# abr.net
KiCad netlist of a schematic drawn in EAGLE
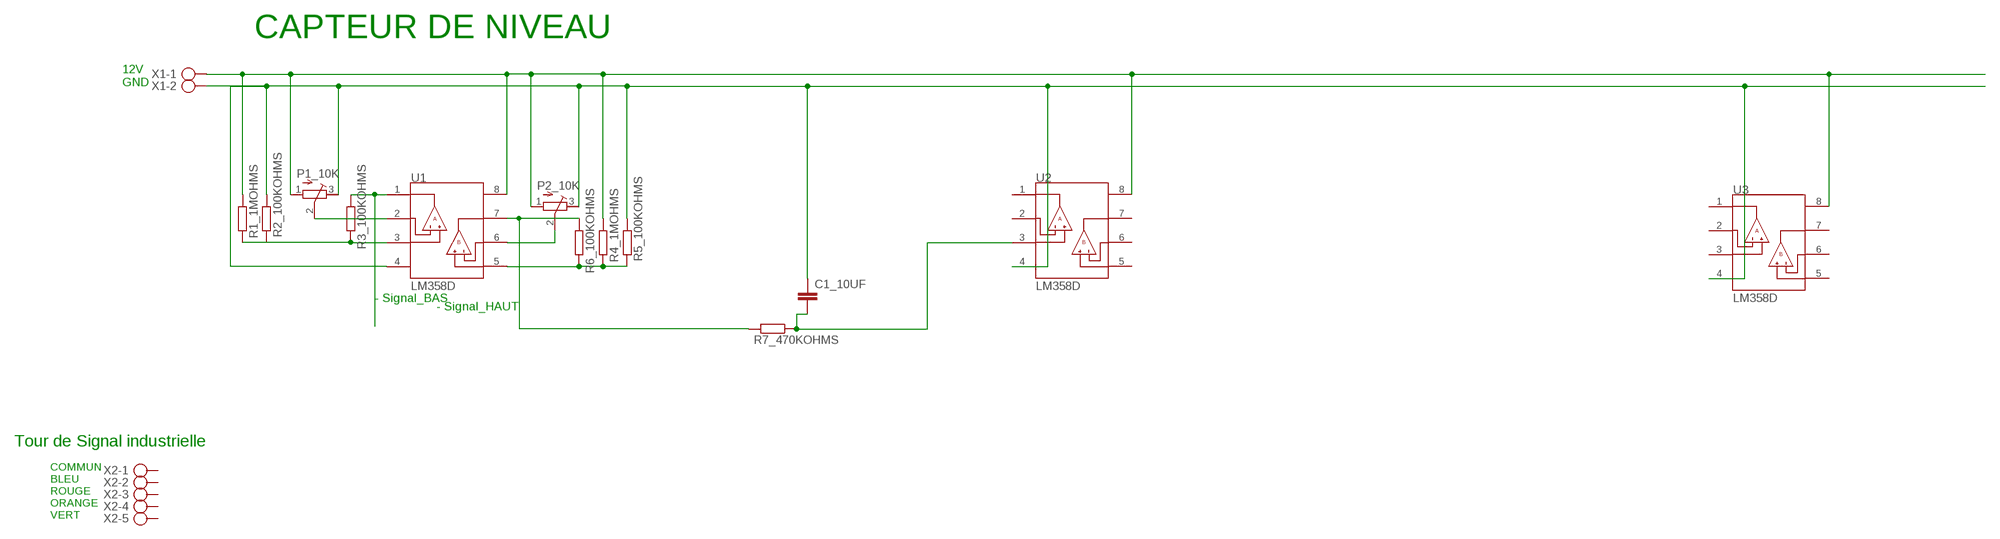
[diagram p0: schematic, sheet 1]

(export (version "E")
  (design (tool "Eeschema 10.0.6"))
  (components
    (comp (ref "C1_10UF")
      (value "C-EU025-025X050")
      (footprint "eagle-import:C025-025X050")
      (libsource (lib "eagle-import") (part "C-EU025-025X050"))
    )
    (comp (ref "P1_10K")
      (value "R-TRIMM3339P")
      (footprint "eagle-import:RTRIM3339P")
      (libsource (lib "eagle-import") (part "R-TRIMM3339P"))
    )
    (comp (ref "P2_10K")
      (value "R-TRIMM3339P")
      (footprint "eagle-import:RTRIM3339P")
      (libsource (lib "eagle-import") (part "R-TRIMM3339P"))
    )
    (comp (ref "R1_1MOHMS")
      (value "R-EU_0207/10")
      (footprint "eagle-import:0207_10")
      (libsource (lib "eagle-import") (part "R-EU_0207/10"))
    )
    (comp (ref "R2_100KOHMS")
      (value "R-EU_0207/10")
      (footprint "eagle-import:0207_10")
      (libsource (lib "eagle-import") (part "R-EU_0207/10"))
    )
    (comp (ref "R3_100KOHMS")
      (value "R-EU_0207/10")
      (footprint "eagle-import:0207_10")
      (libsource (lib "eagle-import") (part "R-EU_0207/10"))
    )
    (comp (ref "R4_1MOHMS")
      (value "R-EU_0207/10")
      (footprint "eagle-import:0207_10")
      (libsource (lib "eagle-import") (part "R-EU_0207/10"))
    )
    (comp (ref "R5_100KOHMS")
      (value "R-EU_0207/10")
      (footprint "eagle-import:0207_10")
      (libsource (lib "eagle-import") (part "R-EU_0207/10"))
    )
    (comp (ref "R6_100KOHMS")
      (value "R-EU_0207/10")
      (footprint "eagle-import:0207_10")
      (libsource (lib "eagle-import") (part "R-EU_0207/10"))
    )
    (comp (ref "R7_470KOHMS")
      (value "R-EU_0207/10")
      (footprint "eagle-import:0207_10")
      (libsource (lib "eagle-import") (part "R-EU_0207/10"))
    )
    (comp (ref "U1")
      (value "LM358D")
      (footprint "eagle-import:SOIC127P599X175-8N")
      (fields (field (name "MF") "STMicroelectronics"))
      (libsource (lib "eagle-import") (part "LM358D"))
    )
    (comp (ref "U2")
      (value "LM358D")
      (footprint "eagle-import:SOIC127P599X175-8N")
      (fields (field (name "MF") "STMicroelectronics"))
      (libsource (lib "eagle-import") (part "LM358D"))
    )
    (comp (ref "U3")
      (value "LM358D")
      (footprint "eagle-import:SOIC127P599X175-8N")
      (fields (field (name "MF") "STMicroelectronics"))
      (libsource (lib "eagle-import") (part "LM358D"))
    )
    (comp (ref "X1")
      (value "AK300/2")
      (footprint "eagle-import:AK300_2")
      (libsource (lib "eagle-import") (part "AK300/2"))
    )
    (comp (ref "X2")
      (value "AK300/5")
      (footprint "eagle-import:AK300_5")
      (libsource (lib "eagle-import") (part "AK300/5"))
    )
  )
  (nets
    (net (code "1") (name "Net-(P1_10K-A)") (class "Default")
      (node (ref "P1_10K") (pin "1") (pinfunction "A_1") (pintype "passive"))
      (node (ref "P2_10K") (pin "1") (pinfunction "A_1") (pintype "passive"))
      (node (ref "R1_1MOHMS") (pin "1") (pinfunction "1_1") (pintype "passive"))
      (node (ref "R4_1MOHMS") (pin "1") (pinfunction "1_1") (pintype "passive"))
      (node (ref "U1") (pin "8") (pinfunction "V+_8") (pintype "power_in"))
      (node (ref "U2") (pin "8") (pinfunction "V+_8") (pintype "power_in"))
      (node (ref "U3") (pin "8") (pinfunction "V+_8") (pintype "power_in"))
      (node (ref "X1") (pin "1") (pinfunction "KL_1") (pintype "passive"))
    )
    (net (code "2") (name "Net-(P1_10K-E)") (class "Default")
      (node (ref "C1_10UF") (pin "1") (pinfunction "1_1") (pintype "passive"))
      (node (ref "P1_10K") (pin "3") (pinfunction "E_3") (pintype "passive"))
      (node (ref "P2_10K") (pin "3") (pinfunction "E_3") (pintype "passive"))
      (node (ref "R2_100KOHMS") (pin "1") (pinfunction "1_1") (pintype "passive"))
      (node (ref "R5_100KOHMS") (pin "1") (pinfunction "1_1") (pintype "passive"))
      (node (ref "U1") (pin "4") (pinfunction "V-_4") (pintype "power_in"))
      (node (ref "U2") (pin "4") (pinfunction "V-_4") (pintype "power_in"))
      (node (ref "U3") (pin "4") (pinfunction "V-_4") (pintype "power_in"))
      (node (ref "X1") (pin "2") (pinfunction "KL_2") (pintype "passive"))
    )
    (net (code "3") (name "Net-(P1_10K-S)") (class "Default")
      (node (ref "P1_10K") (pin "2") (pinfunction "S_2") (pintype "passive"))
      (node (ref "U1") (pin "2") (pinfunction "IN1-_2") (pintype "input"))
    )
    (net (code "4") (name "Net-(P2_10K-S)") (class "Default")
      (node (ref "P2_10K") (pin "2") (pinfunction "S_2") (pintype "passive"))
      (node (ref "U1") (pin "6") (pinfunction "IN2-_6") (pintype "input"))
    )
    (net (code "5") (name "Net-(U1-IN1+)") (class "Default")
      (node (ref "R1_1MOHMS") (pin "2") (pinfunction "2_2") (pintype "passive"))
      (node (ref "R2_100KOHMS") (pin "2") (pinfunction "2_2") (pintype "passive"))
      (node (ref "R3_100KOHMS") (pin "2") (pinfunction "2_2") (pintype "passive"))
      (node (ref "U1") (pin "3") (pinfunction "IN1+_3") (pintype "input"))
    )
    (net (code "6") (name "Net-(U1-IN2+)") (class "Default")
      (node (ref "R4_1MOHMS") (pin "2") (pinfunction "2_2") (pintype "passive"))
      (node (ref "R5_100KOHMS") (pin "2") (pinfunction "2_2") (pintype "passive"))
      (node (ref "R6_100KOHMS") (pin "2") (pinfunction "2_2") (pintype "passive"))
      (node (ref "U1") (pin "5") (pinfunction "IN2+_5") (pintype "input"))
    )
    (net (code "7") (name "Net-(U1-OUT1)") (class "Default")
      (node (ref "R3_100KOHMS") (pin "1") (pinfunction "1_1") (pintype "passive"))
      (node (ref "U1") (pin "1") (pinfunction "OUT1_1") (pintype "output"))
    )
    (net (code "8") (name "Net-(U1-OUT2)") (class "Default")
      (node (ref "R6_100KOHMS") (pin "1") (pinfunction "1_1") (pintype "passive"))
      (node (ref "R7_470KOHMS") (pin "2") (pinfunction "2_2") (pintype "passive"))
      (node (ref "U1") (pin "7") (pinfunction "OUT2_7") (pintype "output"))
    )
    (net (code "9") (name "Net-(U2-IN1+)") (class "Default")
      (node (ref "C1_10UF") (pin "2") (pinfunction "2_2") (pintype "passive"))
      (node (ref "R7_470KOHMS") (pin "1") (pinfunction "1_1") (pintype "passive"))
      (node (ref "U2") (pin "3") (pinfunction "IN1+_3") (pintype "input"))
    )
    (net (code "10") (name "unconnected-(U2-IN1--Pad2)") (class "Default")
      (node (ref "U2") (pin "2") (pinfunction "IN1-_2") (pintype "input"))
    )
    (net (code "11") (name "unconnected-(U2-IN2+-Pad5)") (class "Default")
      (node (ref "U2") (pin "5") (pinfunction "IN2+_5") (pintype "input"))
    )
    (net (code "12") (name "unconnected-(U2-IN2--Pad6)") (class "Default")
      (node (ref "U2") (pin "6") (pinfunction "IN2-_6") (pintype "input"))
    )
    (net (code "13") (name "unconnected-(U2-OUT1-Pad1)") (class "Default")
      (node (ref "U2") (pin "1") (pinfunction "OUT1_1") (pintype "output"))
    )
    (net (code "14") (name "unconnected-(U2-OUT2-Pad7)") (class "Default")
      (node (ref "U2") (pin "7") (pinfunction "OUT2_7") (pintype "output"))
    )
    (net (code "15") (name "unconnected-(U3-IN1+-Pad3)") (class "Default")
      (node (ref "U3") (pin "3") (pinfunction "IN1+_3") (pintype "input"))
    )
    (net (code "16") (name "unconnected-(U3-IN1--Pad2)") (class "Default")
      (node (ref "U3") (pin "2") (pinfunction "IN1-_2") (pintype "input"))
    )
    (net (code "17") (name "unconnected-(U3-IN2+-Pad5)") (class "Default")
      (node (ref "U3") (pin "5") (pinfunction "IN2+_5") (pintype "input"))
    )
    (net (code "18") (name "unconnected-(U3-IN2--Pad6)") (class "Default")
      (node (ref "U3") (pin "6") (pinfunction "IN2-_6") (pintype "input"))
    )
    (net (code "19") (name "unconnected-(U3-OUT1-Pad1)") (class "Default")
      (node (ref "U3") (pin "1") (pinfunction "OUT1_1") (pintype "output"))
    )
    (net (code "20") (name "unconnected-(U3-OUT2-Pad7)") (class "Default")
      (node (ref "U3") (pin "7") (pinfunction "OUT2_7") (pintype "output"))
    )
    (net (code "21") (name "unconnected-(X2A-KL-Pad1)") (class "Default")
      (node (ref "X2") (pin "1") (pinfunction "KL_1") (pintype "passive"))
    )
    (net (code "22") (name "unconnected-(X2B-KL-Pad2)") (class "Default")
      (node (ref "X2") (pin "2") (pinfunction "KL_2") (pintype "passive"))
    )
    (net (code "23") (name "unconnected-(X2C-KL-Pad3)") (class "Default")
      (node (ref "X2") (pin "3") (pinfunction "KL_3") (pintype "passive"))
    )
    (net (code "24") (name "unconnected-(X2D-KL-Pad4)") (class "Default")
      (node (ref "X2") (pin "4") (pinfunction "KL_4") (pintype "passive"))
    )
    (net (code "25") (name "unconnected-(X2E-KL-Pad5)") (class "Default")
      (node (ref "X2") (pin "5") (pinfunction "KL_5") (pintype "passive"))
    )
  )
)
